# CAN_Termination_Board.net
KiCad netlist of a schematic drawn in Altium Designer
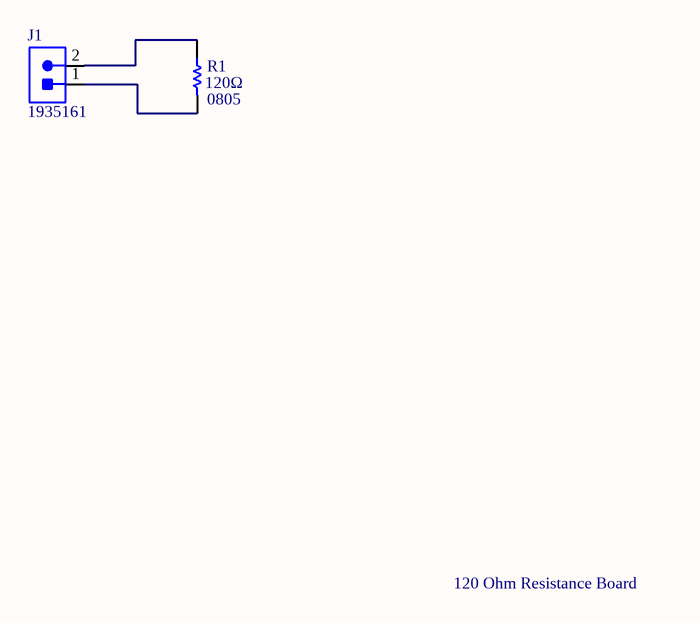
[diagram p0: CAN Termination Board.SchDoc]

(export (version "E")
  (design (tool "Eeschema 10.0.6"))
  (components
    (comp (ref "J1")
      (value "CON_2M_TERM")
      (footprint "1935161")
      (description "TERM BLK 2POS SIDE ENTRY 5MM")
      (fields (field (name "VOLTAGE") "300V") (field (name "MANUFACTURER PART NUMBER 1") "1935161"))
      (libsource (lib "UWRT_Schematic_Library_2020") (part "CON_2M_TERM"))
    )
    (comp (ref "R1")
      (value "RES_120Ω_0805_1%")
      (footprint "RESC0805")
      (description "RES 120 OHM 1% 1/8W 0805")
      (fields
        (field (name "LCSC PART #") "C17437")
        (field (name "PACKAGE/FOOTPRINT") "0805")
        (field (name "RESISTANCE") "120Ω")
      )
      (libsource (lib "UWRT_Schematic_Library_2020") (part "RES_120Ω_0805_1%"))
    )
  )
  (nets
    (net (code "1") (name "Net-(J1-Pad1)") (class "Default")
      (node (ref "J1") (pin "1") (pinfunction "1_1") (pintype "passive"))
      (node (ref "R1") (pin "2") (pinfunction "2_2") (pintype "passive"))
    )
    (net (code "2") (name "Net-(J1-Pad2)") (class "Default")
      (node (ref "J1") (pin "2") (pinfunction "2_2") (pintype "passive"))
      (node (ref "R1") (pin "1") (pinfunction "1_1") (pintype "passive"))
    )
  )
)
